# power_supply.net
KiCad netlist of a schematic drawn in Altium Designer
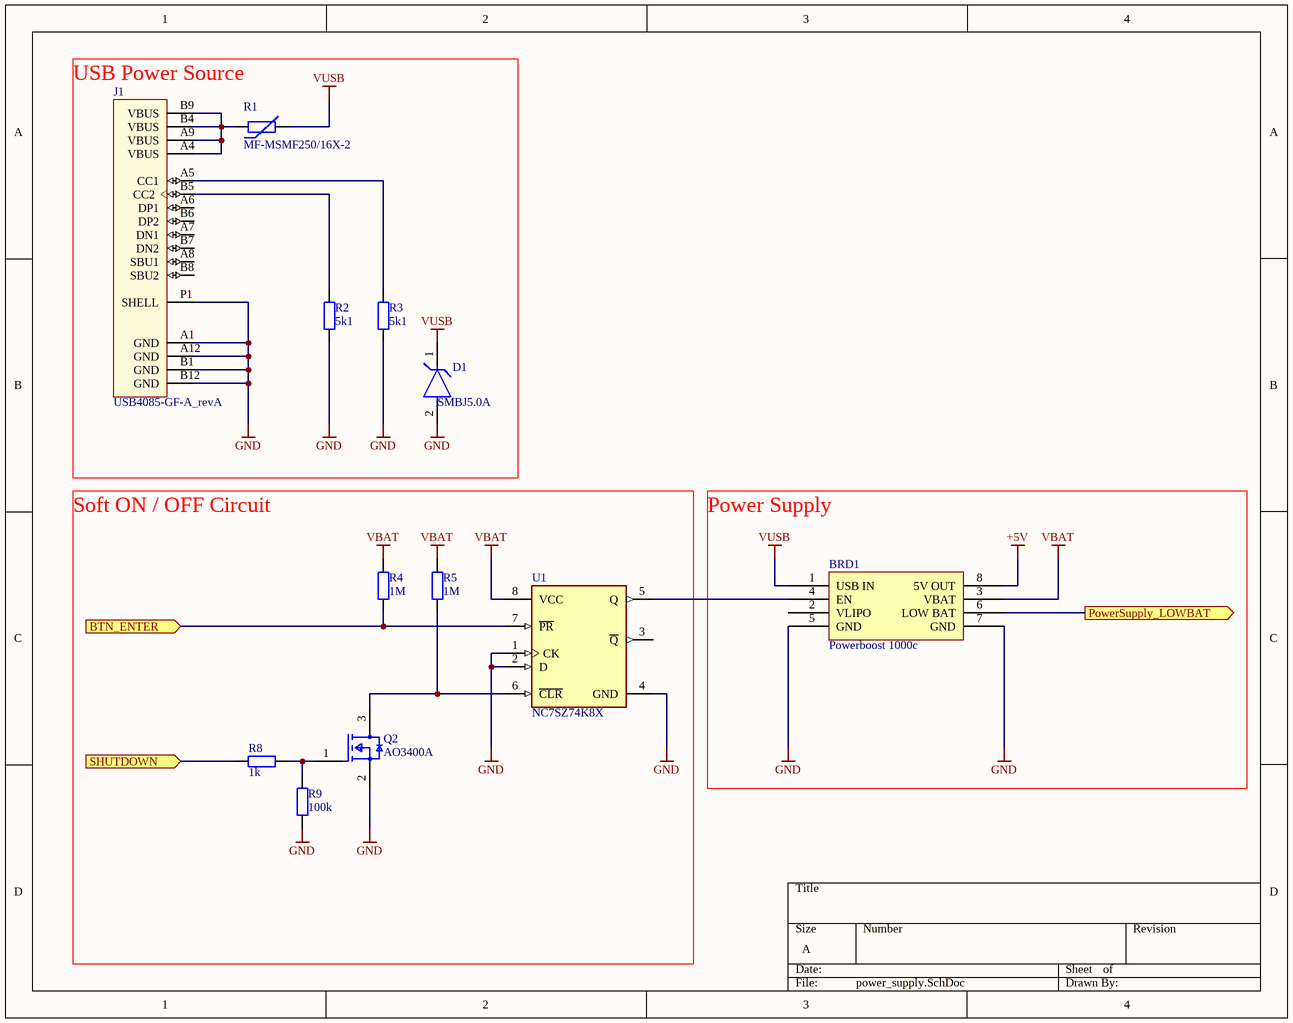
[diagram p0: power_supply.SchDoc]

(export (version "E")
  (design (tool "Eeschema 10.0.6"))
  (components
    (comp (ref "BRD1")
      (value "Powerboost 1000c")
      (footprint "POWERBOOST_1000C")
      (description "BOARD PWRBOOST1000 5V LIPO USB")
      (fields
        (field (name "MANUFACTURER") "Adafruit Industries")
        (field (name "MANUFACTURER PART NUMBER") "2465")
      )
      (libsource (lib "Schlib") (part "Powerboost_1000c"))
    )
    (comp (ref "D1")
      (value "SMBJ5.0A")
      (footprint "FP-SMBJ-MFG")
      (description "TVS DIODE 5V 9.2V DO214AA")
      (fields
        (field (name "OCTOPART") "https://octopart.com/smbj5.0a-littelfuse-8835")
        (field (name "MANUFACTURER") "Littelfuse Inc")
      )
      (libsource (lib "Altium Content Vault") (part "f813f71cba58e380607f5dd3caf9714"))
    )
    (comp (ref "J1")
      (value "USB4085-GF-A_revA")
      (footprint "GCT_USB4085-GF-A_REVA")
      (description "USB 2.0 Type C Receptacle Dip Type, PCB Top Mount")
      (fields (field (name "MANUFACTURER") "Global Connector Technology"))
      (libsource (lib "smart_lamp") (part "USB-C port"))
    )
    (comp (ref "Q2")
      (value "AO3400A")
      (footprint "SOT23")
      (description "MOSFET N-CH 30V 5.7A SOT23")
      (libsource (lib "Schlib") (part "MOSFET_AO3400A"))
    )
    (comp (ref "R1")
      (value "MF-MSMF250/16X-2")
      (footprint "Res_1812")
      (description "PTC Resettable Fuse 2.5A(hold) 5A(trip) 16V 100A 1.2W 5s 0.015Ohm SMD Solder Pad 1812 T/R")
      (fields (field (name "MANUFACTURER") "Bourns"))
      (libsource (lib "smart_lamp") (part "PTC Fuse"))
    )
    (comp (ref "R2")
      (value "5k1")
      (footprint "RESC2013X50X30NL20T20")
      (description "Resistor")
      (fields (field (name "TOLERANCE") "1%") (field (name "Comment") "Res_0805"))
      (libsource (lib "Biral_Generic") (part "Res_0805"))
    )
    (comp (ref "R3")
      (value "5k1")
      (footprint "RESC2013X50X30NL20T20")
      (description "Resistor")
      (fields (field (name "TOLERANCE") "1%") (field (name "Comment") "Res_0805"))
      (libsource (lib "Biral_Generic") (part "Res_0805"))
    )
    (comp (ref "R4")
      (value "1M")
      (footprint "RESC2013X50X30NL20T20")
      (description "Resistor")
      (fields (field (name "TOLERANCE") "1%") (field (name "Comment") "Res_0805"))
      (libsource (lib "Biral_Generic") (part "Res_0805"))
    )
    (comp (ref "R5")
      (value "1M")
      (footprint "RESC2013X50X30NL20T20")
      (description "Resistor")
      (fields (field (name "TOLERANCE") "1%") (field (name "Comment") "Res_0805"))
      (libsource (lib "Biral_Generic") (part "Res_0805"))
    )
    (comp (ref "R8")
      (value "1k")
      (footprint "RESC2013X50X30NL20T20")
      (description "Resistor")
      (fields (field (name "TOLERANCE") "1%") (field (name "Comment") "Res_0805"))
      (libsource (lib "") (part "Res_0805_1"))
    )
    (comp (ref "R9")
      (value "100k")
      (footprint "RESC2013X50X30NL20T20")
      (description "Resistor")
      (fields (field (name "TOLERANCE") "1%") (field (name "Comment") "Res_0805"))
      (libsource (lib "Biral_Generic") (part "Res_0805"))
    )
    (comp (ref "U1")
      (value "NC7SZ74K8X")
      (footprint "FP-846AN-MFG")
      (description "IC FF D-TYPE SNGL 1BIT US8")
      (fields
        (field (name "MANUFACTURER") "ON Semiconductor")
        (field (name "OCTOPART") "https://octopart.com/nc7sz74k8x-on+semiconductor-84330810")
      )
      (libsource (lib "Altium Content Vault") (part "66619382b6644cb22cdf77331785a45"))
    )
  )
  (nets
    (net (code "1") (name "+5V") (class "Default")
      (node (ref "BRD1") (pin "8") (pinfunction "5V_OUT_8") (pintype "passive"))
    )
    (net (code "2") (name "/BTN_ENTER") (class "Default")
      (node (ref "R4") (pin "1") (pinfunction "1_1") (pintype "passive"))
      (node (ref "U1") (pin "7") (pinfunction "~{PR}_7") (pintype "input"))
    )
    (net (code "3") (name "/PowerSupply_LOWBAT") (class "Default")
      (node (ref "BRD1") (pin "6") (pinfunction "LOW_BAT_6") (pintype "passive"))
    )
    (net (code "4") (name "/SHUTDOWN") (class "Default")
      (node (ref "R8") (pin "1") (pinfunction "1_1") (pintype "passive"))
    )
    (net (code "5") (name "GND") (class "Default")
      (node (ref "BRD1") (pin "5") (pinfunction "GND_5") (pintype "passive"))
      (node (ref "BRD1") (pin "7") (pinfunction "GND_7") (pintype "passive"))
      (node (ref "D1") (pin "2") (pinfunction "A_2") (pintype "passive"))
      (node (ref "J1") (pin "A1") (pinfunction "GND_A1") (pintype "power_in"))
      (node (ref "J1") (pin "A12") (pinfunction "GND_A12") (pintype "power_in"))
      (node (ref "J1") (pin "B1") (pinfunction "GND_B1") (pintype "passive"))
      (node (ref "J1") (pin "B12") (pinfunction "GND_B12") (pintype "power_in"))
      (node (ref "J1") (pin "P1") (pinfunction "SHELL_P1") (pintype "passive"))
      (node (ref "Q2") (pin "2") (pinfunction "S_2") (pintype "passive"))
      (node (ref "R2") (pin "1") (pinfunction "1_1") (pintype "passive"))
      (node (ref "R3") (pin "1") (pinfunction "1_1") (pintype "passive"))
      (node (ref "R9") (pin "1") (pinfunction "1_1") (pintype "passive"))
      (node (ref "U1") (pin "1") (pinfunction "CK_1") (pintype "input"))
      (node (ref "U1") (pin "2") (pinfunction "D_2") (pintype "input"))
      (node (ref "U1") (pin "4") (pinfunction "GND_4") (pintype "power_in"))
    )
    (net (code "6") (name "Net-(BRD1-EN)") (class "Default")
      (node (ref "BRD1") (pin "4") (pinfunction "EN_4") (pintype "passive"))
      (node (ref "U1") (pin "5") (pinfunction "Q_5") (pintype "output"))
    )
    (net (code "7") (name "Net-(J1-CC1)") (class "Default")
      (node (ref "J1") (pin "A5") (pinfunction "CC1_A5") (pintype "bidirectional"))
      (node (ref "R3") (pin "2") (pinfunction "2_2") (pintype "passive"))
    )
    (net (code "8") (name "Net-(J1-CC2)") (class "Default")
      (node (ref "J1") (pin "B5") (pinfunction "CC2_B5") (pintype "bidirectional"))
      (node (ref "R2") (pin "2") (pinfunction "2_2") (pintype "passive"))
    )
    (net (code "9") (name "Net-(J1-VBUS-PadA4)") (class "Default")
      (node (ref "J1") (pin "A4") (pinfunction "VBUS_A4") (pintype "power_in"))
      (node (ref "J1") (pin "A9") (pinfunction "VBUS_A9") (pintype "power_in"))
      (node (ref "J1") (pin "B4") (pinfunction "VBUS_B4") (pintype "power_in"))
      (node (ref "J1") (pin "B9") (pinfunction "VBUS_B9") (pintype "power_in"))
      (node (ref "R1") (pin "1") (pinfunction "1_1") (pintype "passive"))
    )
    (net (code "10") (name "Net-(Q2-D)") (class "Default")
      (node (ref "Q2") (pin "3") (pinfunction "D_3") (pintype "passive"))
      (node (ref "R5") (pin "1") (pinfunction "1_1") (pintype "passive"))
      (node (ref "U1") (pin "6") (pinfunction "~{CLR}_6") (pintype "input"))
    )
    (net (code "11") (name "Net-(Q2-G)") (class "Default")
      (node (ref "Q2") (pin "1") (pinfunction "G_1") (pintype "passive"))
      (node (ref "R8") (pin "2") (pinfunction "2_2") (pintype "passive"))
      (node (ref "R9") (pin "2") (pinfunction "2_2") (pintype "passive"))
    )
    (net (code "12") (name "VBAT") (class "Default")
      (node (ref "BRD1") (pin "3") (pinfunction "VBAT_3") (pintype "passive"))
      (node (ref "R4") (pin "2") (pinfunction "2_2") (pintype "passive"))
      (node (ref "R5") (pin "2") (pinfunction "2_2") (pintype "passive"))
      (node (ref "U1") (pin "8") (pinfunction "VCC_8") (pintype "power_in"))
    )
    (net (code "13") (name "VUSB") (class "Default")
      (node (ref "BRD1") (pin "1") (pinfunction "USB_IN_1") (pintype "passive"))
      (node (ref "D1") (pin "1") (pinfunction "C_1") (pintype "passive"))
      (node (ref "R1") (pin "2") (pinfunction "2_2") (pintype "passive"))
    )
    (net (code "14") (name "unconnected-(BRD1-VLIPO-Pad2)") (class "Default")
      (node (ref "BRD1") (pin "2") (pinfunction "VLIPO_2") (pintype "passive"))
    )
    (net (code "15") (name "unconnected-(J1-DN1-PadA7)") (class "Default")
      (node (ref "J1") (pin "A7") (pinfunction "DN1_A7") (pintype "bidirectional"))
    )
    (net (code "16") (name "unconnected-(J1-DN2-PadB7)") (class "Default")
      (node (ref "J1") (pin "B7") (pinfunction "DN2_B7") (pintype "bidirectional"))
    )
    (net (code "17") (name "unconnected-(J1-DP1-PadA6)") (class "Default")
      (node (ref "J1") (pin "A6") (pinfunction "DP1_A6") (pintype "bidirectional"))
    )
    (net (code "18") (name "unconnected-(J1-DP2-PadB6)") (class "Default")
      (node (ref "J1") (pin "B6") (pinfunction "DP2_B6") (pintype "bidirectional"))
    )
    (net (code "19") (name "unconnected-(J1-SBU1-PadA8)") (class "Default")
      (node (ref "J1") (pin "A8") (pinfunction "SBU1_A8") (pintype "bidirectional"))
    )
    (net (code "20") (name "unconnected-(J1-SBU2-PadB8)") (class "Default")
      (node (ref "J1") (pin "B8") (pinfunction "SBU2_B8") (pintype "bidirectional"))
    )
    (net (code "21") (name "unconnected-(U1-~{Q}-Pad3)") (class "Default")
      (node (ref "U1") (pin "3") (pinfunction "~{Q}_3") (pintype "output"))
    )
  )
)
